# Antenna.net
KiCad netlist of a schematic drawn in Altium Designer
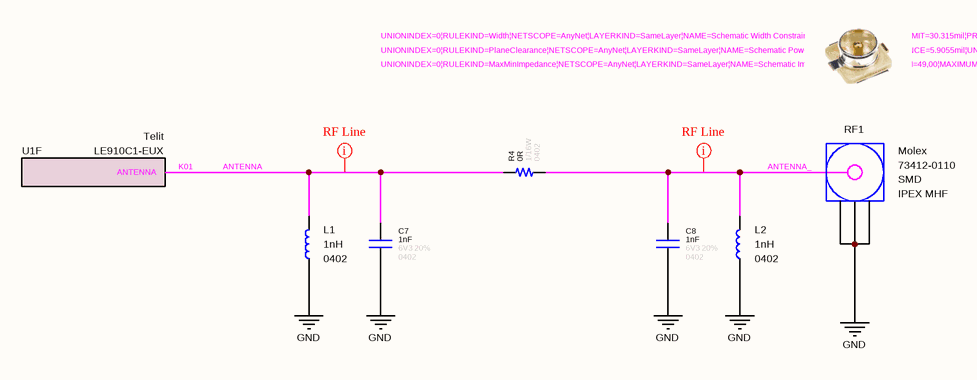
[diagram p0: Antenna.SchDoc]

(export (version "E")
  (design (tool "Eeschema 10.0.6"))
  (components
    (comp (ref "C7")
      (value "1nF")
      (footprint "CAPACITOR_0402")
      (description "Capacitor - 1nF [0402] (Ceramic)")
      (fields
        (field (name "MANUFACTURER PART NUMBER") "04026C102MAT2A")
        (field (name "TOLERANCE") "20%")
        (field (name "CASE") "0402")
        (field (name "VOLTAGE") "6V3")
      )
      (libsource (lib "P101DA_Library") (part "Capacitor - 1nF [0402-6V3]"))
    )
    (comp (ref "C8")
      (value "1nF")
      (footprint "CAPACITOR_0402")
      (description "Capacitor - 1nF [0402] (Ceramic)")
      (fields
        (field (name "MANUFACTURER PART NUMBER") "04026C102MAT2A")
        (field (name "TOLERANCE") "20%")
        (field (name "CASE") "0402")
        (field (name "VOLTAGE") "6V3")
      )
      (libsource (lib "P101DA_Library") (part "Capacitor - 1nF [0402-6V3]"))
    )
    (comp (ref "L1")
      (value "1nH")
      (footprint "INDUCTOR_0402")
      (description "Fixed Inductor")
      (fields
        (field (name "MANUFACTURER PART NUMBER") "LQG15HN1N0S02D")
        (field (name "TOLERANCE") "0.3 nH")
        (field (name "CASE") "0402")
      )
      (libsource (lib "P101DA_Library") (part "Inductor - 1nH [0402]"))
    )
    (comp (ref "L2")
      (value "1nH")
      (footprint "INDUCTOR_0402")
      (description "Fixed Inductor")
      (fields
        (field (name "MANUFACTURER PART NUMBER") "LQG15HN1N0S02D")
        (field (name "TOLERANCE") "0.3 nH")
        (field (name "CASE") "0402")
      )
      (libsource (lib "P101DA_Library") (part "Inductor - 1nH [0402]"))
    )
    (comp (ref "R4")
      (value "0R")
      (footprint "RESISTOR_0402")
      (description "Thick Film Resistors - SMD 1/16 W 0 Ohm")
      (fields
        (field (name "MANUFACTURER PART NUMBER") "CRCW04020000Z0ED")
        (field (name "CASE") "0402")
        (field (name "POWER") "1/16W")
        (field (name "Comment") "0R - 0402 - %1 - 1/16W")
      )
      (libsource (lib "P101DA_Library") (part "Resistor - 0R [0402]"))
    )
    (comp (ref "RF1")
      (value "73412-0110")
      (footprint "Connector_IPEX")
      (description "MOLEX   73412-0110   RF COAXIAL, MICROCOAXIAL, JACK, 50OHM")
      (fields
        (field (name "CONNECTOR TYPE") "IPEX MHF")
        (field (name "CASE") "SMD")
        (field (name "MANUFACTURER PART NUMBER") "73412-0110")
        (field (name "MANUFACTURER NAME") "Molex")
      )
      (libsource (lib "P101DA_Library") (part "Connector - IPEX MHF"))
    )
    (comp (ref "U1")
      (value "LE910C1-EUX LTE GSM Module")
      (footprint "LE910 GSM Modem")
      (description "Telit LE910C1-EUX LTE/2G GSM Module")
      (fields
        (field (name "MANUFACTURER PART NUMBER") "LE910C1-EUX")
        (field (name "MANUFACTURER NAME") "Telit")
      )
      (libsource (lib "Akkoyun") (part "IC - LE910C1-EUX"))
    )
  )
  (nets
    (net (code "1") (name "/ANTENNA") (class "Default")
      (node (ref "C7") (pin "2") (pinfunction "2_2") (pintype "passive"))
      (node (ref "L1") (pin "2") (pinfunction "2_2") (pintype "passive"))
      (node (ref "R4") (pin "2") (pinfunction "2_2") (pintype "passive"))
      (node (ref "U1") (pin "K01") (pinfunction "ANTENNA_K01") (pintype "passive"))
    )
    (net (code "2") (name "/ANTENNA_") (class "Default")
      (node (ref "C8") (pin "2") (pinfunction "2_2") (pintype "passive"))
      (node (ref "L2") (pin "2") (pinfunction "2_2") (pintype "passive"))
      (node (ref "R4") (pin "1") (pinfunction "1_1") (pintype "passive"))
      (node (ref "RF1") (pin "1") (pinfunction "Signal_1") (pintype "passive"))
    )
    (net (code "3") (name "GND") (class "Default")
      (node (ref "C7") (pin "1") (pinfunction "1_1") (pintype "passive"))
      (node (ref "C8") (pin "1") (pinfunction "1_1") (pintype "passive"))
      (node (ref "L1") (pin "1") (pinfunction "1_1") (pintype "passive"))
      (node (ref "L2") (pin "1") (pinfunction "1_1") (pintype "passive"))
      (node (ref "RF1") (pin "2") (pinfunction "GND_2") (pintype "passive"))
      (node (ref "RF1") (pin "3") (pinfunction "GND_3") (pintype "passive"))
      (node (ref "RF1") (pin "4") (pinfunction "GND_4") (pintype "passive"))
    )
  )
)
